# ESP8266-01-Breakout.net
KiCad netlist of a schematic drawn in Altium Designer
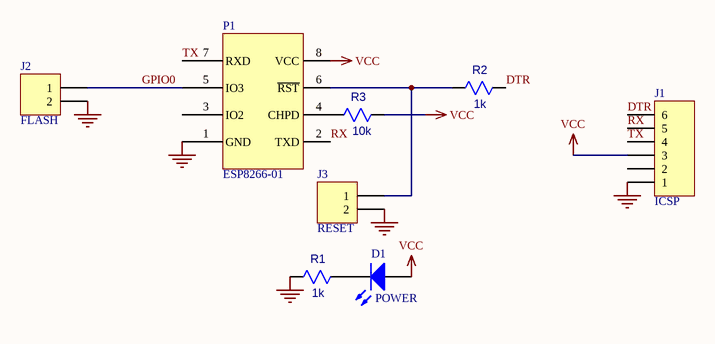
[diagram p0: ESP8266-01-Breakout.SchDoc]

(export (version "E")
  (design (tool "Eeschema 10.0.6"))
  (components
    (comp (ref "D1")
      (value "POWER")
      (footprint "3.2X1.6X1.1")
      (description "Typical RED, GREEN, YELLOW, AMBER GaAs LED")
      (fields (field (name "PUBLISHER") "Altium Limited"))
      (libsource (lib "Miscellaneous Devices") (part "LED2"))
    )
    (comp (ref "J1")
      (value "ICSP")
      (footprint "HDR1X6")
      (description "Header, 6-Pin")
      (fields (field (name "PUBLISHER") "Altium Limited"))
      (libsource (lib "Miscellaneous Connectors") (part "Header 6"))
    )
    (comp (ref "J2")
      (value "FLASH")
      (footprint "HDR1X2")
      (description "Header, 2-Pin")
      (fields (field (name "PUBLISHER") "Altium Limited"))
      (libsource (lib "Miscellaneous Connectors") (part "Header 2"))
    )
    (comp (ref "J3")
      (value "RESET")
      (footprint "HDR1X2")
      (description "Header, 2-Pin")
      (fields (field (name "PUBLISHER") "Altium Limited"))
      (libsource (lib "Miscellaneous Connectors") (part "Header 2"))
    )
    (comp (ref "P1")
      (value "ESP8266-01")
      (footprint "ESP8266-01")
      (libsource (lib "ESP8266-01-Breakout") (part "ESP8266-01"))
    )
    (comp (ref "R1")
      (value "1k")
      (footprint "CAPC0805(2012)75_N")
      (description "RES_0805")
      (libsource (lib "AltiumIntegratedLibrary") (part "RES_0805"))
    )
    (comp (ref "R2")
      (value "1k")
      (footprint "CAPC0805(2012)75_N")
      (description "RES_0805")
      (libsource (lib "AltiumIntegratedLibrary") (part "RES_0805"))
    )
    (comp (ref "R3")
      (value "10k")
      (footprint "CAPC0805(2012)75_N")
      (description "RES_0805")
      (libsource (lib "AltiumIntegratedLibrary") (part "RES_0805"))
    )
  )
  (nets
    (net (code "1") (name "/DTR") (class "Default")
      (node (ref "J1") (pin "6") (pinfunction "6_6") (pintype "passive"))
      (node (ref "R2") (pin "1") (pintype "passive"))
    )
    (net (code "2") (name "/GPIO0") (class "Default")
      (node (ref "J2") (pin "1") (pinfunction "1_1") (pintype "passive"))
      (node (ref "P1") (pin "5") (pinfunction "IO3_5") (pintype "passive"))
    )
    (net (code "3") (name "/RX") (class "Default")
      (node (ref "J1") (pin "5") (pinfunction "5_5") (pintype "passive"))
      (node (ref "P1") (pin "2") (pinfunction "TXD_2") (pintype "passive"))
    )
    (net (code "4") (name "/TX") (class "Default")
      (node (ref "J1") (pin "4") (pinfunction "4_4") (pintype "passive"))
      (node (ref "P1") (pin "7") (pinfunction "RXD_7") (pintype "passive"))
    )
    (net (code "5") (name "GND") (class "Default")
      (node (ref "J1") (pin "1") (pinfunction "1_1") (pintype "passive"))
      (node (ref "J2") (pin "2") (pinfunction "2_2") (pintype "passive"))
      (node (ref "J3") (pin "2") (pinfunction "2_2") (pintype "passive"))
      (node (ref "P1") (pin "1") (pinfunction "GND_1") (pintype "passive"))
      (node (ref "R1") (pin "2") (pintype "passive"))
    )
    (net (code "6") (name "Net-(D1-K)") (class "Default")
      (node (ref "D1") (pin "2") (pinfunction "K_2") (pintype "passive"))
      (node (ref "R1") (pin "1") (pintype "passive"))
    )
    (net (code "7") (name "Net-(P1-CHPD)") (class "Default")
      (node (ref "P1") (pin "4") (pinfunction "CHPD_4") (pintype "passive"))
      (node (ref "R3") (pin "2") (pintype "passive"))
    )
    (net (code "8") (name "Net-(P1-~{RST})") (class "Default")
      (node (ref "J3") (pin "1") (pinfunction "1_1") (pintype "passive"))
      (node (ref "P1") (pin "6") (pinfunction "~{RST}_6") (pintype "passive"))
      (node (ref "R2") (pin "2") (pintype "passive"))
    )
    (net (code "9") (name "VCC") (class "Default")
      (node (ref "D1") (pin "1") (pinfunction "A_1") (pintype "passive"))
      (node (ref "J1") (pin "3") (pinfunction "3_3") (pintype "passive"))
      (node (ref "P1") (pin "8") (pinfunction "VCC_8") (pintype "passive"))
      (node (ref "R3") (pin "1") (pintype "passive"))
    )
    (net (code "10") (name "unconnected-(J1-Pad2)") (class "Default")
      (node (ref "J1") (pin "2") (pinfunction "2_2") (pintype "passive"))
    )
    (net (code "11") (name "unconnected-(P1-IO2-Pad3)") (class "Default")
      (node (ref "P1") (pin "3") (pinfunction "IO2_3") (pintype "passive"))
    )
  )
)
